# Relay_Cape.net
KiCad netlist of a schematic drawn in EAGLE
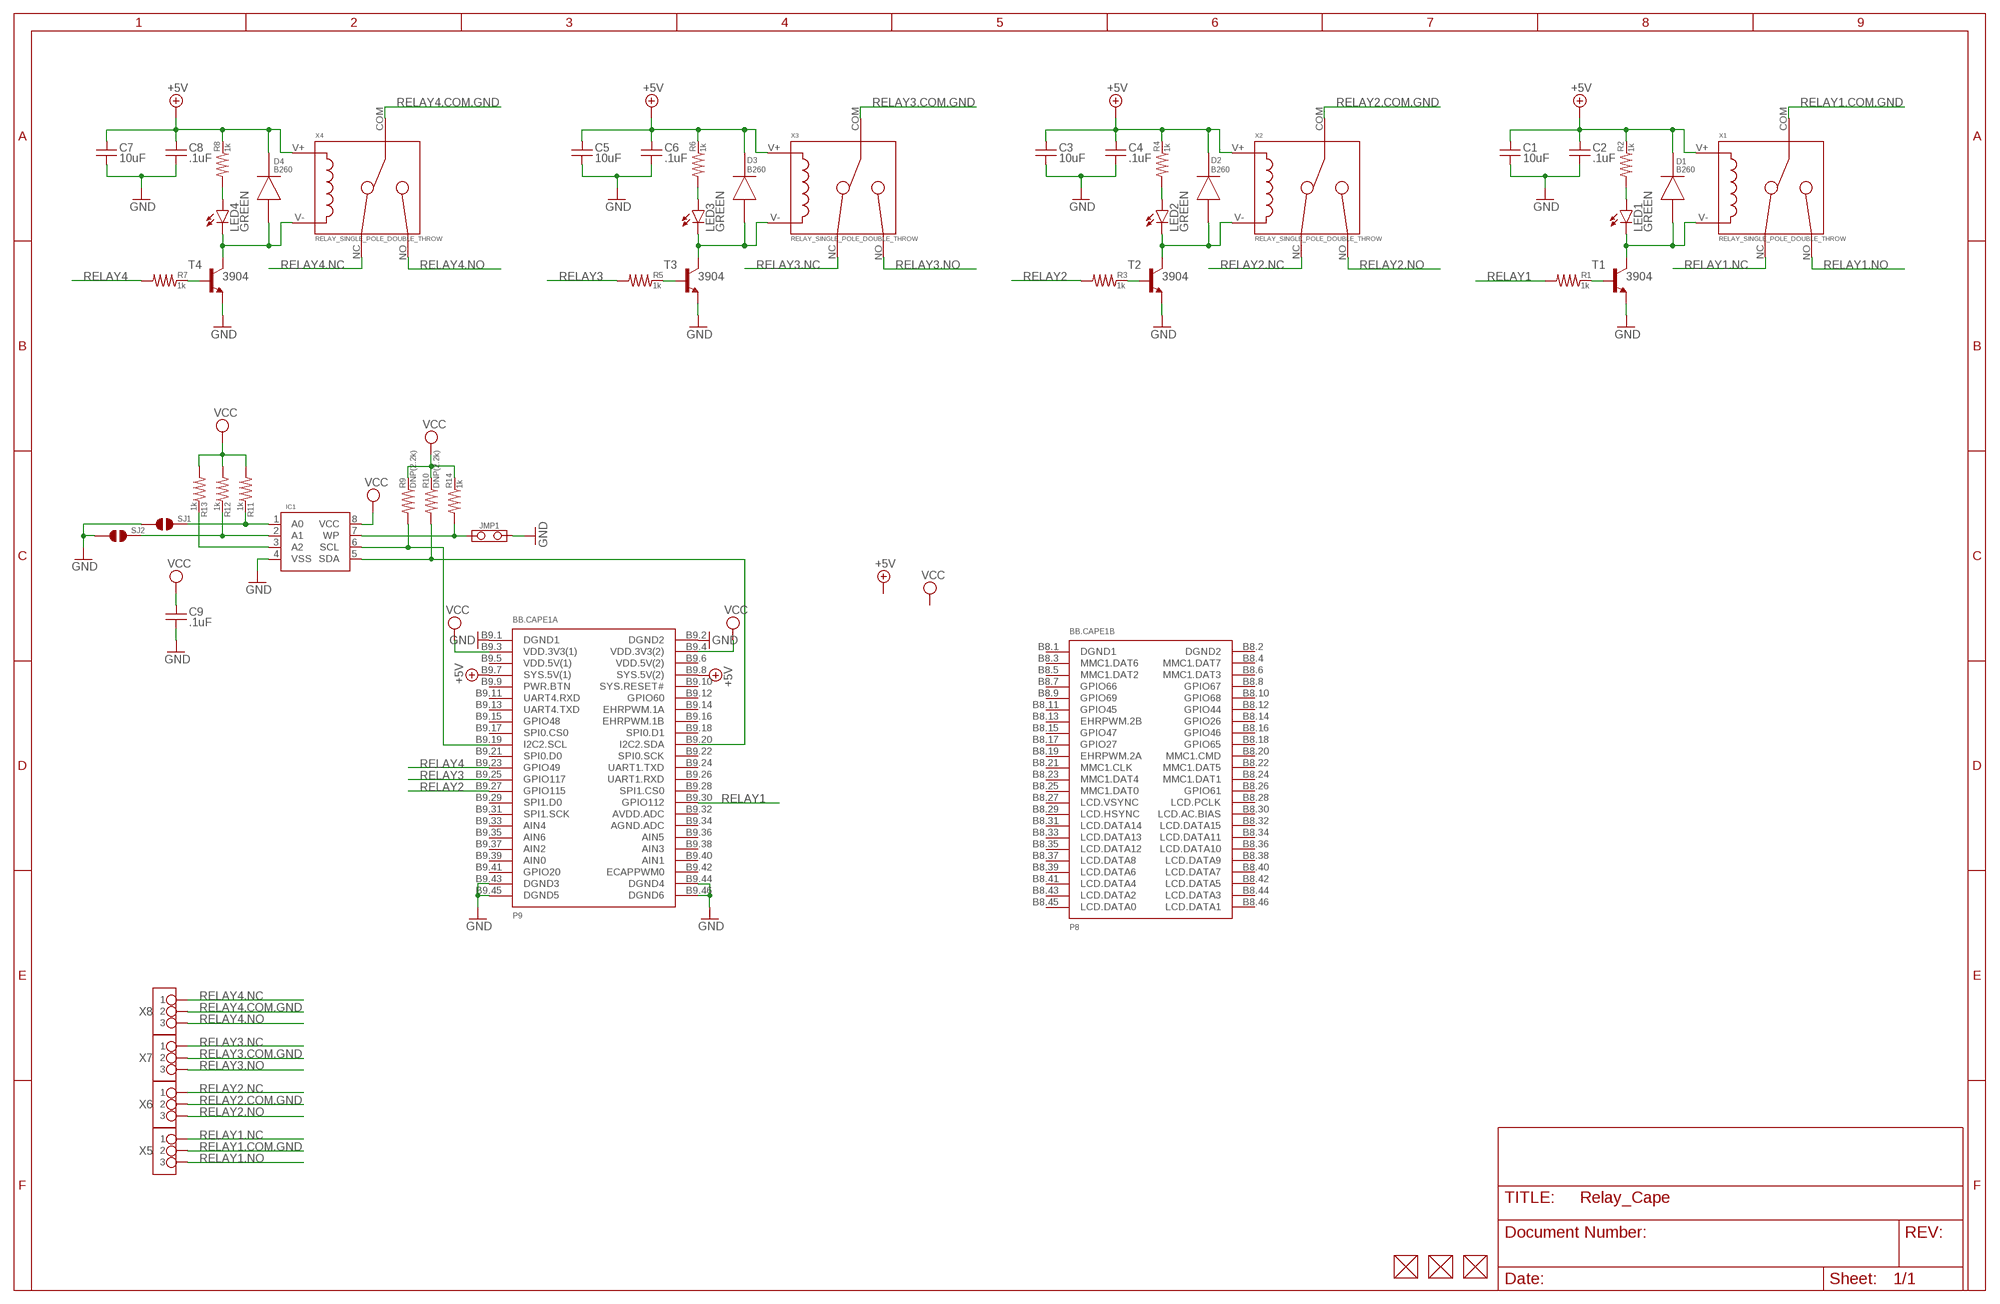
[diagram p0: schematic, sheet 1]

(export (version "E")
  (design (tool "Eeschema 10.0.6"))
  (components
    (comp (ref "BB.CAPE1")
      (value "BEAGLEBONE.CAPE.BOTTOM-ONLY-PADS")
      (footprint "eagle-import:BEAGLEBONE.CAPE.BOTTOM-ONLY-PADS")
      (libsource (lib "eagle-import") (part "BEAGLEBONE.CAPE.BOTTOM-ONLY-PADS"))
    )
    (comp (ref "C1")
      (value "10uF")
      (footprint "eagle-import:0805")
      (libsource (lib "eagle-import") (part "CAPACITOR-(INCH)-0805"))
    )
    (comp (ref "C2")
      (value ".1uF")
      (footprint "eagle-import:0402")
      (libsource (lib "eagle-import") (part "CAPACITOR-(INCH)-0402"))
    )
    (comp (ref "C3")
      (value "10uF")
      (footprint "eagle-import:0805")
      (libsource (lib "eagle-import") (part "CAPACITOR-(INCH)-0805"))
    )
    (comp (ref "C4")
      (value ".1uF")
      (footprint "eagle-import:0402")
      (libsource (lib "eagle-import") (part "CAPACITOR-(INCH)-0402"))
    )
    (comp (ref "C5")
      (value "10uF")
      (footprint "eagle-import:0805")
      (libsource (lib "eagle-import") (part "CAPACITOR-(INCH)-0805"))
    )
    (comp (ref "C6")
      (value ".1uF")
      (footprint "eagle-import:0402")
      (libsource (lib "eagle-import") (part "CAPACITOR-(INCH)-0402"))
    )
    (comp (ref "C7")
      (value "10uF")
      (footprint "eagle-import:0805")
      (libsource (lib "eagle-import") (part "CAPACITOR-(INCH)-0805"))
    )
    (comp (ref "C8")
      (value ".1uF")
      (footprint "eagle-import:0402")
      (libsource (lib "eagle-import") (part "CAPACITOR-(INCH)-0402"))
    )
    (comp (ref "C9")
      (value ".1uF")
      (footprint "eagle-import:0402")
      (libsource (lib "eagle-import") (part "CAPACITOR-(INCH)-0402"))
    )
    (comp (ref "D1")
      (value "B260")
      (footprint "eagle-import:DIODE_SMA")
      (libsource (lib "eagle-import") (part "DIODE_SMA"))
    )
    (comp (ref "D2")
      (value "B260")
      (footprint "eagle-import:DIODE_SMA")
      (libsource (lib "eagle-import") (part "DIODE_SMA"))
    )
    (comp (ref "D3")
      (value "B260")
      (footprint "eagle-import:DIODE_SMA")
      (libsource (lib "eagle-import") (part "DIODE_SMA"))
    )
    (comp (ref "D4")
      (value "B260")
      (footprint "eagle-import:DIODE_SMA")
      (libsource (lib "eagle-import") (part "DIODE_SMA"))
    )
    (comp (ref "FUD1")
      (value "FIDUCIAL")
      (footprint "eagle-import:FIDUCIAL_40MIL")
      (libsource (lib "eagle-import") (part "FIDUCIAL"))
    )
    (comp (ref "FUD2")
      (value "FIDUCIAL")
      (footprint "eagle-import:FIDUCIAL_40MIL")
      (libsource (lib "eagle-import") (part "FIDUCIAL"))
    )
    (comp (ref "FUD3")
      (value "FIDUCIAL")
      (footprint "eagle-import:FIDUCIAL_40MIL")
      (libsource (lib "eagle-import") (part "FIDUCIAL"))
    )
    (comp (ref "IC1")
      (value "CAT24C32")
      (footprint "eagle-import:UDFN8,2X3(ON-SEMI)")
      (libsource (lib "eagle-import") (part "CAT24C32"))
    )
    (comp (ref "JMP1")
      (value "JUMPER-(X2)")
      (footprint "eagle-import:JUMPER-(X2)")
      (libsource (lib "eagle-import") (part "JUMPER-(X2)"))
    )
    (comp (ref "LED1")
      (value "GREEN")
      (footprint "eagle-import:0805-LED")
      (libsource (lib "eagle-import") (part "LED-(INCH)-0805"))
    )
    (comp (ref "LED2")
      (value "GREEN")
      (footprint "eagle-import:0805-LED")
      (libsource (lib "eagle-import") (part "LED-(INCH)-0805"))
    )
    (comp (ref "LED3")
      (value "GREEN")
      (footprint "eagle-import:0805-LED")
      (libsource (lib "eagle-import") (part "LED-(INCH)-0805"))
    )
    (comp (ref "LED4")
      (value "GREEN")
      (footprint "eagle-import:0805-LED")
      (libsource (lib "eagle-import") (part "LED-(INCH)-0805"))
    )
    (comp (ref "R1")
      (value "1k")
      (footprint "eagle-import:0603")
      (libsource (lib "eagle-import") (part "RESISTOR-(INCH)-0603"))
    )
    (comp (ref "R2")
      (value "1k")
      (footprint "eagle-import:0603")
      (libsource (lib "eagle-import") (part "RESISTOR-(INCH)-0603"))
    )
    (comp (ref "R3")
      (value "1k")
      (footprint "eagle-import:0603")
      (libsource (lib "eagle-import") (part "RESISTOR-(INCH)-0603"))
    )
    (comp (ref "R4")
      (value "1k")
      (footprint "eagle-import:0603")
      (libsource (lib "eagle-import") (part "RESISTOR-(INCH)-0603"))
    )
    (comp (ref "R5")
      (value "1k")
      (footprint "eagle-import:0603")
      (libsource (lib "eagle-import") (part "RESISTOR-(INCH)-0603"))
    )
    (comp (ref "R6")
      (value "1k")
      (footprint "eagle-import:0603")
      (libsource (lib "eagle-import") (part "RESISTOR-(INCH)-0603"))
    )
    (comp (ref "R7")
      (value "1k")
      (footprint "eagle-import:0603")
      (libsource (lib "eagle-import") (part "RESISTOR-(INCH)-0603"))
    )
    (comp (ref "R8")
      (value "1k")
      (footprint "eagle-import:0603")
      (libsource (lib "eagle-import") (part "RESISTOR-(INCH)-0603"))
    )
    (comp (ref "R9")
      (value "DNP(2.2k)")
      (footprint "eagle-import:0402")
      (libsource (lib "eagle-import") (part "RESISTOR-(INCH)-0402"))
    )
    (comp (ref "R10")
      (value "DNP(2.2k)")
      (footprint "eagle-import:0402")
      (libsource (lib "eagle-import") (part "RESISTOR-(INCH)-0402"))
    )
    (comp (ref "R11")
      (value "1k")
      (footprint "eagle-import:0402")
      (libsource (lib "eagle-import") (part "RESISTOR-(INCH)-0402"))
    )
    (comp (ref "R12")
      (value "1k")
      (footprint "eagle-import:0402")
      (libsource (lib "eagle-import") (part "RESISTOR-(INCH)-0402"))
    )
    (comp (ref "R13")
      (value "1k")
      (footprint "eagle-import:0402")
      (libsource (lib "eagle-import") (part "RESISTOR-(INCH)-0402"))
    )
    (comp (ref "R14")
      (value "1k")
      (footprint "eagle-import:0402")
      (libsource (lib "eagle-import") (part "RESISTOR-(INCH)-0402"))
    )
    (comp (ref "SJ1")
      (value "SOLDER.JOINT-(INCH)-0603")
      (footprint "eagle-import:SOLDER.JOINT(0603)")
      (libsource (lib "eagle-import") (part "SOLDER.JOINT-(INCH)-0603"))
    )
    (comp (ref "SJ2")
      (value "SOLDER.JOINT-(INCH)-0603")
      (footprint "eagle-import:SOLDER.JOINT(0603)")
      (libsource (lib "eagle-import") (part "SOLDER.JOINT-(INCH)-0603"))
    )
    (comp (ref "T1")
      (value "3904")
      (footprint "eagle-import:SOT23-BEC")
      (libsource (lib "eagle-import") (part "-NPN-SOT23-BECBC847"))
    )
    (comp (ref "T2")
      (value "3904")
      (footprint "eagle-import:SOT23-BEC")
      (libsource (lib "eagle-import") (part "-NPN-SOT23-BECBC847"))
    )
    (comp (ref "T3")
      (value "3904")
      (footprint "eagle-import:SOT23-BEC")
      (libsource (lib "eagle-import") (part "-NPN-SOT23-BECBC847"))
    )
    (comp (ref "T4")
      (value "3904")
      (footprint "eagle-import:SOT23-BEC")
      (libsource (lib "eagle-import") (part "-NPN-SOT23-BECBC847"))
    )
    (comp (ref "X1")
      (value "RELAY_SINGLE_POLE_DOUBLE_THROW")
      (footprint "eagle-import:GOODSKY.RWH-SH-105D")
      (libsource (lib "eagle-import") (part "RELAY_SINGLE_POLE_DOUBLE_THROW"))
    )
    (comp (ref "X2")
      (value "RELAY_SINGLE_POLE_DOUBLE_THROW")
      (footprint "eagle-import:GOODSKY.RWH-SH-105D")
      (libsource (lib "eagle-import") (part "RELAY_SINGLE_POLE_DOUBLE_THROW"))
    )
    (comp (ref "X3")
      (value "RELAY_SINGLE_POLE_DOUBLE_THROW")
      (footprint "eagle-import:GOODSKY.RWH-SH-105D")
      (libsource (lib "eagle-import") (part "RELAY_SINGLE_POLE_DOUBLE_THROW"))
    )
    (comp (ref "X4")
      (value "RELAY_SINGLE_POLE_DOUBLE_THROW")
      (footprint "eagle-import:GOODSKY.RWH-SH-105D")
      (libsource (lib "eagle-import") (part "RELAY_SINGLE_POLE_DOUBLE_THROW"))
    )
    (comp (ref "X5")
      (value "TB-3TERM-5MM.PITCH-(50MIL.HOLES)")
      (footprint "eagle-import:TERMINAL.BLOCK-3TERM-5MM.PITCH-(50MIL.HOLES)")
      (libsource (lib "eagle-import") (part "TB-3TERM-5MM.PITCH-(50MIL.HOLES)"))
    )
    (comp (ref "X6")
      (value "TB-3TERM-5MM.PITCH-(50MIL.HOLES)")
      (footprint "eagle-import:TERMINAL.BLOCK-3TERM-5MM.PITCH-(50MIL.HOLES)")
      (libsource (lib "eagle-import") (part "TB-3TERM-5MM.PITCH-(50MIL.HOLES)"))
    )
    (comp (ref "X7")
      (value "TB-3TERM-5MM.PITCH-(50MIL.HOLES)")
      (footprint "eagle-import:TERMINAL.BLOCK-3TERM-5MM.PITCH-(50MIL.HOLES)")
      (libsource (lib "eagle-import") (part "TB-3TERM-5MM.PITCH-(50MIL.HOLES)"))
    )
    (comp (ref "X8")
      (value "TB-3TERM-5MM.PITCH-(50MIL.HOLES)")
      (footprint "eagle-import:TERMINAL.BLOCK-3TERM-5MM.PITCH-(50MIL.HOLES)")
      (libsource (lib "eagle-import") (part "TB-3TERM-5MM.PITCH-(50MIL.HOLES)"))
    )
  )
  (nets
    (net (code "1") (name "+5V") (class "Default")
      (node (ref "BB.CAPE1") (pin "B9.7") (pinfunction "SYS.5V(1)_B9.7") (pintype "bidirectional"))
      (node (ref "BB.CAPE1") (pin "B9.8") (pinfunction "SYS.5V(2)_B9.8") (pintype "bidirectional"))
      (node (ref "C1") (pin "1") (pinfunction "1_1") (pintype "bidirectional"))
      (node (ref "C2") (pin "1") (pinfunction "1_1") (pintype "bidirectional"))
      (node (ref "C3") (pin "1") (pinfunction "1_1") (pintype "bidirectional"))
      (node (ref "C4") (pin "1") (pinfunction "1_1") (pintype "bidirectional"))
      (node (ref "C5") (pin "1") (pinfunction "1_1") (pintype "bidirectional"))
      (node (ref "C6") (pin "1") (pinfunction "1_1") (pintype "bidirectional"))
      (node (ref "C7") (pin "1") (pinfunction "1_1") (pintype "bidirectional"))
      (node (ref "C8") (pin "1") (pinfunction "1_1") (pintype "bidirectional"))
      (node (ref "D1") (pin "K") (pinfunction "K_K") (pintype "bidirectional"))
      (node (ref "D2") (pin "K") (pinfunction "K_K") (pintype "bidirectional"))
      (node (ref "D3") (pin "K") (pinfunction "K_K") (pintype "bidirectional"))
      (node (ref "D4") (pin "K") (pinfunction "K_K") (pintype "bidirectional"))
      (node (ref "R2") (pin "2") (pinfunction "2_2") (pintype "bidirectional"))
      (node (ref "R4") (pin "2") (pinfunction "2_2") (pintype "bidirectional"))
      (node (ref "R6") (pin "2") (pinfunction "2_2") (pintype "bidirectional"))
      (node (ref "R8") (pin "2") (pinfunction "2_2") (pintype "bidirectional"))
      (node (ref "X1") (pin "V+") (pinfunction "V+_V+") (pintype "bidirectional"))
      (node (ref "X2") (pin "V+") (pinfunction "V+_V+") (pintype "bidirectional"))
      (node (ref "X3") (pin "V+") (pinfunction "V+_V+") (pintype "bidirectional"))
      (node (ref "X4") (pin "V+") (pinfunction "V+_V+") (pintype "bidirectional"))
    )
    (net (code "2") (name "/RELAY1") (class "Default")
      (node (ref "BB.CAPE1") (pin "B9.30") (pinfunction "GPIO112_B9.30") (pintype "bidirectional"))
      (node (ref "R1") (pin "1") (pinfunction "1_1") (pintype "bidirectional"))
    )
    (net (code "3") (name "/RELAY1.COM.GND") (class "Default")
      (node (ref "X1") (pin "COM") (pinfunction "COM_COM") (pintype "bidirectional"))
      (node (ref "X5") (pin "2") (pinfunction "2_2") (pintype "bidirectional"))
    )
    (net (code "4") (name "/RELAY1.NC") (class "Default")
      (node (ref "X1") (pin "NC") (pinfunction "NC_NC") (pintype "bidirectional"))
      (node (ref "X5") (pin "1") (pinfunction "1_1") (pintype "bidirectional"))
    )
    (net (code "5") (name "/RELAY1.NO") (class "Default")
      (node (ref "X1") (pin "NO") (pinfunction "NO_NO") (pintype "bidirectional"))
      (node (ref "X5") (pin "3") (pinfunction "3_3") (pintype "bidirectional"))
    )
    (net (code "6") (name "/RELAY2") (class "Default")
      (node (ref "BB.CAPE1") (pin "B9.27") (pinfunction "GPIO115_B9.27") (pintype "bidirectional"))
      (node (ref "R3") (pin "1") (pinfunction "1_1") (pintype "bidirectional"))
    )
    (net (code "7") (name "/RELAY2.COM.GND") (class "Default")
      (node (ref "X2") (pin "COM") (pinfunction "COM_COM") (pintype "bidirectional"))
      (node (ref "X6") (pin "2") (pinfunction "2_2") (pintype "bidirectional"))
    )
    (net (code "8") (name "/RELAY2.NC") (class "Default")
      (node (ref "X2") (pin "NC") (pinfunction "NC_NC") (pintype "bidirectional"))
      (node (ref "X6") (pin "1") (pinfunction "1_1") (pintype "bidirectional"))
    )
    (net (code "9") (name "/RELAY2.NO") (class "Default")
      (node (ref "X2") (pin "NO") (pinfunction "NO_NO") (pintype "bidirectional"))
      (node (ref "X6") (pin "3") (pinfunction "3_3") (pintype "bidirectional"))
    )
    (net (code "10") (name "/RELAY3") (class "Default")
      (node (ref "BB.CAPE1") (pin "B9.25") (pinfunction "GPIO117_B9.25") (pintype "bidirectional"))
      (node (ref "R5") (pin "1") (pinfunction "1_1") (pintype "bidirectional"))
    )
    (net (code "11") (name "/RELAY3.COM.GND") (class "Default")
      (node (ref "X3") (pin "COM") (pinfunction "COM_COM") (pintype "bidirectional"))
      (node (ref "X7") (pin "2") (pinfunction "2_2") (pintype "bidirectional"))
    )
    (net (code "12") (name "/RELAY3.NC") (class "Default")
      (node (ref "X3") (pin "NC") (pinfunction "NC_NC") (pintype "bidirectional"))
      (node (ref "X7") (pin "1") (pinfunction "1_1") (pintype "bidirectional"))
    )
    (net (code "13") (name "/RELAY3.NO") (class "Default")
      (node (ref "X3") (pin "NO") (pinfunction "NO_NO") (pintype "bidirectional"))
      (node (ref "X7") (pin "3") (pinfunction "3_3") (pintype "bidirectional"))
    )
    (net (code "14") (name "/RELAY4") (class "Default")
      (node (ref "BB.CAPE1") (pin "B9.23") (pinfunction "GPIO49_B9.23") (pintype "bidirectional"))
      (node (ref "R7") (pin "1") (pinfunction "1_1") (pintype "bidirectional"))
    )
    (net (code "15") (name "/RELAY4.COM.GND") (class "Default")
      (node (ref "X4") (pin "COM") (pinfunction "COM_COM") (pintype "bidirectional"))
      (node (ref "X8") (pin "2") (pinfunction "2_2") (pintype "bidirectional"))
    )
    (net (code "16") (name "/RELAY4.NC") (class "Default")
      (node (ref "X4") (pin "NC") (pinfunction "NC_NC") (pintype "bidirectional"))
      (node (ref "X8") (pin "1") (pinfunction "1_1") (pintype "bidirectional"))
    )
    (net (code "17") (name "/RELAY4.NO") (class "Default")
      (node (ref "X4") (pin "NO") (pinfunction "NO_NO") (pintype "bidirectional"))
      (node (ref "X8") (pin "3") (pinfunction "3_3") (pintype "bidirectional"))
    )
    (net (code "18") (name "GND") (class "Default")
      (node (ref "BB.CAPE1") (pin "B9.1") (pinfunction "DGND1_B9.1") (pintype "bidirectional"))
      (node (ref "BB.CAPE1") (pin "B9.2") (pinfunction "DGND2_B9.2") (pintype "bidirectional"))
      (node (ref "BB.CAPE1") (pin "B9.43") (pinfunction "DGND3_B9.43") (pintype "bidirectional"))
      (node (ref "BB.CAPE1") (pin "B9.44") (pinfunction "DGND4_B9.44") (pintype "bidirectional"))
      (node (ref "BB.CAPE1") (pin "B9.45") (pinfunction "DGND5_B9.45") (pintype "bidirectional"))
      (node (ref "BB.CAPE1") (pin "B9.46") (pinfunction "DGND6_B9.46") (pintype "bidirectional"))
      (node (ref "C1") (pin "2") (pinfunction "2_2") (pintype "bidirectional"))
      (node (ref "C2") (pin "2") (pinfunction "2_2") (pintype "bidirectional"))
      (node (ref "C3") (pin "2") (pinfunction "2_2") (pintype "bidirectional"))
      (node (ref "C4") (pin "2") (pinfunction "2_2") (pintype "bidirectional"))
      (node (ref "C5") (pin "2") (pinfunction "2_2") (pintype "bidirectional"))
      (node (ref "C6") (pin "2") (pinfunction "2_2") (pintype "bidirectional"))
      (node (ref "C7") (pin "2") (pinfunction "2_2") (pintype "bidirectional"))
      (node (ref "C8") (pin "2") (pinfunction "2_2") (pintype "bidirectional"))
      (node (ref "C9") (pin "2") (pinfunction "2_2") (pintype "bidirectional"))
      (node (ref "IC1") (pin "4") (pinfunction "VSS_4") (pintype "bidirectional"))
      (node (ref "JMP1") (pin "2") (pinfunction "2_2") (pintype "bidirectional"))
      (node (ref "SJ1") (pin "1") (pinfunction "1_1") (pintype "bidirectional"))
      (node (ref "SJ2") (pin "1") (pinfunction "1_1") (pintype "bidirectional"))
      (node (ref "T1") (pin "E") (pinfunction "E_E") (pintype "passive"))
      (node (ref "T2") (pin "E") (pinfunction "E_E") (pintype "passive"))
      (node (ref "T3") (pin "E") (pinfunction "E_E") (pintype "passive"))
      (node (ref "T4") (pin "E") (pinfunction "E_E") (pintype "passive"))
    )
    (net (code "19") (name "Net-(BB.CAPE1A-I2C2.SCL)") (class "Default")
      (node (ref "BB.CAPE1") (pin "B9.19") (pinfunction "I2C2.SCL_B9.19") (pintype "bidirectional"))
      (node (ref "IC1") (pin "6") (pinfunction "SCL_6") (pintype "bidirectional"))
      (node (ref "R9") (pin "1") (pinfunction "1_1") (pintype "bidirectional"))
    )
    (net (code "20") (name "Net-(BB.CAPE1A-I2C2.SDA)") (class "Default")
      (node (ref "BB.CAPE1") (pin "B9.20") (pinfunction "I2C2.SDA_B9.20") (pintype "bidirectional"))
      (node (ref "IC1") (pin "5") (pinfunction "SDA_5") (pintype "bidirectional"))
      (node (ref "R10") (pin "1") (pinfunction "1_1") (pintype "bidirectional"))
    )
    (net (code "21") (name "Net-(D1-PadA)") (class "Default")
      (node (ref "D1") (pin "A") (pinfunction "A_A") (pintype "bidirectional"))
      (node (ref "LED1") (pin "K") (pinfunction "K_K") (pintype "passive"))
      (node (ref "T1") (pin "C") (pinfunction "C_C") (pintype "passive"))
      (node (ref "X1") (pin "V-") (pinfunction "V-_V-") (pintype "bidirectional"))
    )
    (net (code "22") (name "Net-(D2-PadA)") (class "Default")
      (node (ref "D2") (pin "A") (pinfunction "A_A") (pintype "bidirectional"))
      (node (ref "LED2") (pin "K") (pinfunction "K_K") (pintype "passive"))
      (node (ref "T2") (pin "C") (pinfunction "C_C") (pintype "passive"))
      (node (ref "X2") (pin "V-") (pinfunction "V-_V-") (pintype "bidirectional"))
    )
    (net (code "23") (name "Net-(D3-PadA)") (class "Default")
      (node (ref "D3") (pin "A") (pinfunction "A_A") (pintype "bidirectional"))
      (node (ref "LED3") (pin "K") (pinfunction "K_K") (pintype "passive"))
      (node (ref "T3") (pin "C") (pinfunction "C_C") (pintype "passive"))
      (node (ref "X3") (pin "V-") (pinfunction "V-_V-") (pintype "bidirectional"))
    )
    (net (code "24") (name "Net-(D4-PadA)") (class "Default")
      (node (ref "D4") (pin "A") (pinfunction "A_A") (pintype "bidirectional"))
      (node (ref "LED4") (pin "K") (pinfunction "K_K") (pintype "passive"))
      (node (ref "T4") (pin "C") (pinfunction "C_C") (pintype "passive"))
      (node (ref "X4") (pin "V-") (pinfunction "V-_V-") (pintype "bidirectional"))
    )
    (net (code "25") (name "Net-(IC1-A0)") (class "Default")
      (node (ref "IC1") (pin "1") (pinfunction "A0_1") (pintype "bidirectional"))
      (node (ref "R11") (pin "2") (pinfunction "2_2") (pintype "bidirectional"))
      (node (ref "SJ1") (pin "2") (pinfunction "2_2") (pintype "bidirectional"))
    )
    (net (code "26") (name "Net-(IC1-A1)") (class "Default")
      (node (ref "IC1") (pin "2") (pinfunction "A1_2") (pintype "bidirectional"))
      (node (ref "R12") (pin "2") (pinfunction "2_2") (pintype "bidirectional"))
      (node (ref "SJ2") (pin "2") (pinfunction "2_2") (pintype "bidirectional"))
    )
    (net (code "27") (name "Net-(IC1-A2)") (class "Default")
      (node (ref "IC1") (pin "3") (pinfunction "A2_3") (pintype "bidirectional"))
      (node (ref "R13") (pin "2") (pinfunction "2_2") (pintype "bidirectional"))
    )
    (net (code "28") (name "Net-(IC1-WP)") (class "Default")
      (node (ref "IC1") (pin "7") (pinfunction "WP_7") (pintype "bidirectional"))
      (node (ref "JMP1") (pin "1") (pinfunction "1_1") (pintype "bidirectional"))
      (node (ref "R14") (pin "1") (pinfunction "1_1") (pintype "bidirectional"))
    )
    (net (code "29") (name "Net-(LED1-PadA)") (class "Default")
      (node (ref "LED1") (pin "A") (pinfunction "A_A") (pintype "passive"))
      (node (ref "R2") (pin "1") (pinfunction "1_1") (pintype "bidirectional"))
    )
    (net (code "30") (name "Net-(LED2-PadA)") (class "Default")
      (node (ref "LED2") (pin "A") (pinfunction "A_A") (pintype "passive"))
      (node (ref "R4") (pin "1") (pinfunction "1_1") (pintype "bidirectional"))
    )
    (net (code "31") (name "Net-(LED3-PadA)") (class "Default")
      (node (ref "LED3") (pin "A") (pinfunction "A_A") (pintype "passive"))
      (node (ref "R6") (pin "1") (pinfunction "1_1") (pintype "bidirectional"))
    )
    (net (code "32") (name "Net-(LED4-PadA)") (class "Default")
      (node (ref "LED4") (pin "A") (pinfunction "A_A") (pintype "passive"))
      (node (ref "R8") (pin "1") (pinfunction "1_1") (pintype "bidirectional"))
    )
    (net (code "33") (name "Net-(R1-Pad2)") (class "Default")
      (node (ref "R1") (pin "2") (pinfunction "2_2") (pintype "bidirectional"))
      (node (ref "T1") (pin "B") (pinfunction "B_B") (pintype "passive"))
    )
    (net (code "34") (name "Net-(R3-Pad2)") (class "Default")
      (node (ref "R3") (pin "2") (pinfunction "2_2") (pintype "bidirectional"))
      (node (ref "T2") (pin "B") (pinfunction "B_B") (pintype "passive"))
    )
    (net (code "35") (name "Net-(R5-Pad2)") (class "Default")
      (node (ref "R5") (pin "2") (pinfunction "2_2") (pintype "bidirectional"))
      (node (ref "T3") (pin "B") (pinfunction "B_B") (pintype "passive"))
    )
    (net (code "36") (name "Net-(R7-Pad2)") (class "Default")
      (node (ref "R7") (pin "2") (pinfunction "2_2") (pintype "bidirectional"))
      (node (ref "T4") (pin "B") (pinfunction "B_B") (pintype "passive"))
    )
    (net (code "37") (name "VCC") (class "Default")
      (node (ref "BB.CAPE1") (pin "B9.3") (pinfunction "VDD.3V3(1)_B9.3") (pintype "bidirectional"))
      (node (ref "BB.CAPE1") (pin "B9.4") (pinfunction "VDD.3V3(2)_B9.4") (pintype "bidirectional"))
      (node (ref "C9") (pin "1") (pinfunction "1_1") (pintype "bidirectional"))
      (node (ref "IC1") (pin "8") (pinfunction "VCC_8") (pintype "bidirectional"))
      (node (ref "R10") (pin "2") (pinfunction "2_2") (pintype "bidirectional"))
      (node (ref "R11") (pin "1") (pinfunction "1_1") (pintype "bidirectional"))
      (node (ref "R12") (pin "1") (pinfunction "1_1") (pintype "bidirectional"))
      (node (ref "R13") (pin "1") (pinfunction "1_1") (pintype "bidirectional"))
      (node (ref "R14") (pin "2") (pinfunction "2_2") (pintype "bidirectional"))
      (node (ref "R9") (pin "2") (pinfunction "2_2") (pintype "bidirectional"))
    )
    (net (code "38") (name "unconnected-(BB.CAPE1A-AGND.ADC-PadB9.34)") (class "Default")
      (node (ref "BB.CAPE1") (pin "B9.34") (pinfunction "AGND.ADC_B9.34") (pintype "bidirectional"))
    )
    (net (code "39") (name "unconnected-(BB.CAPE1A-AIN0-PadB9.39)") (class "Default")
      (node (ref "BB.CAPE1") (pin "B9.39") (pinfunction "AIN0_B9.39") (pintype "bidirectional"))
    )
    (net (code "40") (name "unconnected-(BB.CAPE1A-AIN1-PadB9.40)") (class "Default")
      (node (ref "BB.CAPE1") (pin "B9.40") (pinfunction "AIN1_B9.40") (pintype "bidirectional"))
    )
    (net (code "41") (name "unconnected-(BB.CAPE1A-AIN2-PadB9.37)") (class "Default")
      (node (ref "BB.CAPE1") (pin "B9.37") (pinfunction "AIN2_B9.37") (pintype "bidirectional"))
    )
    (net (code "42") (name "unconnected-(BB.CAPE1A-AIN3-PadB9.38)") (class "Default")
      (node (ref "BB.CAPE1") (pin "B9.38") (pinfunction "AIN3_B9.38") (pintype "bidirectional"))
    )
    (net (code "43") (name "unconnected-(BB.CAPE1A-AIN4-PadB9.33)") (class "Default")
      (node (ref "BB.CAPE1") (pin "B9.33") (pinfunction "AIN4_B9.33") (pintype "bidirectional"))
    )
    (net (code "44") (name "unconnected-(BB.CAPE1A-AIN5-PadB9.36)") (class "Default")
      (node (ref "BB.CAPE1") (pin "B9.36") (pinfunction "AIN5_B9.36") (pintype "bidirectional"))
    )
    (net (code "45") (name "unconnected-(BB.CAPE1A-AIN6-PadB9.35)") (class "Default")
      (node (ref "BB.CAPE1") (pin "B9.35") (pinfunction "AIN6_B9.35") (pintype "bidirectional"))
    )
    (net (code "46") (name "unconnected-(BB.CAPE1A-AVDD.ADC-PadB9.32)") (class "Default")
      (node (ref "BB.CAPE1") (pin "B9.32") (pinfunction "AVDD.ADC_B9.32") (pintype "bidirectional"))
    )
    (net (code "47") (name "unconnected-(BB.CAPE1A-ECAPPWM0-PadB9.42)") (class "Default")
      (node (ref "BB.CAPE1") (pin "B9.42") (pinfunction "ECAPPWM0_B9.42") (pintype "bidirectional"))
    )
    (net (code "48") (name "unconnected-(BB.CAPE1A-EHRPWM.1A-PadB9.14)") (class "Default")
      (node (ref "BB.CAPE1") (pin "B9.14") (pinfunction "EHRPWM.1A_B9.14") (pintype "bidirectional"))
    )
    (net (code "49") (name "unconnected-(BB.CAPE1A-EHRPWM.1B-PadB9.16)") (class "Default")
      (node (ref "BB.CAPE1") (pin "B9.16") (pinfunction "EHRPWM.1B_B9.16") (pintype "bidirectional"))
    )
    (net (code "50") (name "unconnected-(BB.CAPE1A-GPIO20-PadB9.41)") (class "Default")
      (node (ref "BB.CAPE1") (pin "B9.41") (pinfunction "GPIO20_B9.41") (pintype "bidirectional"))
    )
    (net (code "51") (name "unconnected-(BB.CAPE1A-GPIO48-PadB9.15)") (class "Default")
      (node (ref "BB.CAPE1") (pin "B9.15") (pinfunction "GPIO48_B9.15") (pintype "bidirectional"))
    )
    (net (code "52") (name "unconnected-(BB.CAPE1A-GPIO60-PadB9.12)") (class "Default")
      (node (ref "BB.CAPE1") (pin "B9.12") (pinfunction "GPIO60_B9.12") (pintype "bidirectional"))
    )
    (net (code "53") (name "unconnected-(BB.CAPE1A-PWR.BTN-PadB9.9)") (class "Default")
      (node (ref "BB.CAPE1") (pin "B9.9") (pinfunction "PWR.BTN_B9.9") (pintype "bidirectional"))
    )
    (net (code "54") (name "unconnected-(BB.CAPE1A-SPI0.CS0-PadB9.17)") (class "Default")
      (node (ref "BB.CAPE1") (pin "B9.17") (pinfunction "SPI0.CS0_B9.17") (pintype "bidirectional"))
    )
    (net (code "55") (name "unconnected-(BB.CAPE1A-SPI0.D0-PadB9.21)") (class "Default")
      (node (ref "BB.CAPE1") (pin "B9.21") (pinfunction "SPI0.D0_B9.21") (pintype "bidirectional"))
    )
    (net (code "56") (name "unconnected-(BB.CAPE1A-SPI0.D1-PadB9.18)") (class "Default")
      (node (ref "BB.CAPE1") (pin "B9.18") (pinfunction "SPI0.D1_B9.18") (pintype "bidirectional"))
    )
    (net (code "57") (name "unconnected-(BB.CAPE1A-SPI0.SCK-PadB9.22)") (class "Default")
      (node (ref "BB.CAPE1") (pin "B9.22") (pinfunction "SPI0.SCK_B9.22") (pintype "bidirectional"))
    )
    (net (code "58") (name "unconnected-(BB.CAPE1A-SPI1.CS0-PadB9.28)") (class "Default")
      (node (ref "BB.CAPE1") (pin "B9.28") (pinfunction "SPI1.CS0_B9.28") (pintype "bidirectional"))
    )
    (net (code "59") (name "unconnected-(BB.CAPE1A-SPI1.D0-PadB9.29)") (class "Default")
      (node (ref "BB.CAPE1") (pin "B9.29") (pinfunction "SPI1.D0_B9.29") (pintype "bidirectional"))
    )
    (net (code "60") (name "unconnected-(BB.CAPE1A-SPI1.SCK-PadB9.31)") (class "Default")
      (node (ref "BB.CAPE1") (pin "B9.31") (pinfunction "SPI1.SCK_B9.31") (pintype "bidirectional"))
    )
    (net (code "61") (name "unconnected-(BB.CAPE1A-SYS.RESET#-PadB9.10)") (class "Default")
      (node (ref "BB.CAPE1") (pin "B9.10") (pinfunction "SYS.RESET#_B9.10") (pintype "bidirectional"))
    )
    (net (code "62") (name "unconnected-(BB.CAPE1A-UART1.RXD-PadB9.26)") (class "Default")
      (node (ref "BB.CAPE1") (pin "B9.26") (pinfunction "UART1.RXD_B9.26") (pintype "bidirectional"))
    )
    (net (code "63") (name "unconnected-(BB.CAPE1A-UART1.TXD-PadB9.24)") (class "Default")
      (node (ref "BB.CAPE1") (pin "B9.24") (pinfunction "UART1.TXD_B9.24") (pintype "bidirectional"))
    )
    (net (code "64") (name "unconnected-(BB.CAPE1A-UART4.RXD-PadB9.11)") (class "Default")
      (node (ref "BB.CAPE1") (pin "B9.11") (pinfunction "UART4.RXD_B9.11") (pintype "bidirectional"))
    )
    (net (code "65") (name "unconnected-(BB.CAPE1A-UART4.TXD-PadB9.13)") (class "Default")
      (node (ref "BB.CAPE1") (pin "B9.13") (pinfunction "UART4.TXD_B9.13") (pintype "bidirectional"))
    )
    (net (code "66") (name "unconnected-(BB.CAPE1A-VDD.5V(1)-PadB9.5)") (class "Default")
      (node (ref "BB.CAPE1") (pin "B9.5") (pinfunction "VDD.5V(1)_B9.5") (pintype "bidirectional"))
    )
    (net (code "67") (name "unconnected-(BB.CAPE1A-VDD.5V(2)-PadB9.6)") (class "Default")
      (node (ref "BB.CAPE1") (pin "B9.6") (pinfunction "VDD.5V(2)_B9.6") (pintype "bidirectional"))
    )
    (net (code "68") (name "unconnected-(BB.CAPE1B-DGND1-PadB8.1)") (class "Default")
      (node (ref "BB.CAPE1") (pin "B8.1") (pinfunction "DGND1_B8.1") (pintype "bidirectional"))
    )
    (net (code "69") (name "unconnected-(BB.CAPE1B-DGND2-PadB8.2)") (class "Default")
      (node (ref "BB.CAPE1") (pin "B8.2") (pinfunction "DGND2_B8.2") (pintype "bidirectional"))
    )
    (net (code "70") (name "unconnected-(BB.CAPE1B-EHRPWM.2A-PadB8.19)") (class "Default")
      (node (ref "BB.CAPE1") (pin "B8.19") (pinfunction "EHRPWM.2A_B8.19") (pintype "bidirectional"))
    )
    (net (code "71") (name "unconnected-(BB.CAPE1B-EHRPWM.2B-PadB8.13)") (class "Default")
      (node (ref "BB.CAPE1") (pin "B8.13") (pinfunction "EHRPWM.2B_B8.13") (pintype "bidirectional"))
    )
    (net (code "72") (name "unconnected-(BB.CAPE1B-GPIO26-PadB8.14)") (class "Default")
      (node (ref "BB.CAPE1") (pin "B8.14") (pinfunction "GPIO26_B8.14") (pintype "bidirectional"))
    )
    (net (code "73") (name "unconnected-(BB.CAPE1B-GPIO27-PadB8.17)") (class "Default")
      (node (ref "BB.CAPE1") (pin "B8.17") (pinfunction "GPIO27_B8.17") (pintype "bidirectional"))
    )
    (net (code "74") (name "unconnected-(BB.CAPE1B-GPIO44-PadB8.12)") (class "Default")
      (node (ref "BB.CAPE1") (pin "B8.12") (pinfunction "GPIO44_B8.12") (pintype "bidirectional"))
    )
    (net (code "75") (name "unconnected-(BB.CAPE1B-GPIO45-PadB8.11)") (class "Default")
      (node (ref "BB.CAPE1") (pin "B8.11") (pinfunction "GPIO45_B8.11") (pintype "bidirectional"))
    )
    (net (code "76") (name "unconnected-(BB.CAPE1B-GPIO46-PadB8.16)") (class "Default")
      (node (ref "BB.CAPE1") (pin "B8.16") (pinfunction "GPIO46_B8.16") (pintype "bidirectional"))
    )
    (net (code "77") (name "unconnected-(BB.CAPE1B-GPIO47-PadB8.15)") (class "Default")
      (node (ref "BB.CAPE1") (pin "B8.15") (pinfunction "GPIO47_B8.15") (pintype "bidirectional"))
    )
    (net (code "78") (name "unconnected-(BB.CAPE1B-GPIO61-PadB8.26)") (class "Default")
      (node (ref "BB.CAPE1") (pin "B8.26") (pinfunction "GPIO61_B8.26") (pintype "bidirectional"))
    )
    (net (code "79") (name "unconnected-(BB.CAPE1B-GPIO65-PadB8.18)") (class "Default")
      (node (ref "BB.CAPE1") (pin "B8.18") (pinfunction "GPIO65_B8.18") (pintype "bidirectional"))
    )
    (net (code "80") (name "unconnected-(BB.CAPE1B-GPIO66-PadB8.7)") (class "Default")
      (node (ref "BB.CAPE1") (pin "B8.7") (pinfunction "GPIO66_B8.7") (pintype "bidirectional"))
    )
    (net (code "81") (name "unconnected-(BB.CAPE1B-GPIO67-PadB8.8)") (class "Default")
      (node (ref "BB.CAPE1") (pin "B8.8") (pinfunction "GPIO67_B8.8") (pintype "bidirectional"))
    )
    (net (code "82") (name "unconnected-(BB.CAPE1B-GPIO68-PadB8.10)") (class "Default")
      (node (ref "BB.CAPE1") (pin "B8.10") (pinfunction "GPIO68_B8.10") (pintype "bidirectional"))
    )
    (net (code "83") (name "unconnected-(BB.CAPE1B-GPIO69-PadB8.9)") (class "Default")
      (node (ref "BB.CAPE1") (pin "B8.9") (pinfunction "GPIO69_B8.9") (pintype "bidirectional"))
    )
    (net (code "84") (name "unconnected-(BB.CAPE1B-LCD.AC.BIAS-PadB8.30)") (class "Default")
      (node (ref "BB.CAPE1") (pin "B8.30") (pinfunction "LCD.AC.BIAS_B8.30") (pintype "bidirectional"))
    )
    (net (code "85") (name "unconnected-(BB.CAPE1B-LCD.DATA0-PadB8.45)") (class "Default")
      (node (ref "BB.CAPE1") (pin "B8.45") (pinfunction "LCD.DATA0_B8.45") (pintype "bidirectional"))
    )
    (net (code "86") (name "unconnected-(BB.CAPE1B-LCD.DATA1-PadB8.46)") (class "Default")
      (node (ref "BB.CAPE1") (pin "B8.46") (pinfunction "LCD.DATA1_B8.46") (pintype "bidirectional"))
    )
    (net (code "87") (name "unconnected-(BB.CAPE1B-LCD.DATA2-PadB8.43)") (class "Default")
      (node (ref "BB.CAPE1") (pin "B8.43") (pinfunction "LCD.DATA2_B8.43") (pintype "bidirectional"))
    )
    (net (code "88") (name "unconnected-(BB.CAPE1B-LCD.DATA3-PadB8.44)") (class "Default")
      (node (ref "BB.CAPE1") (pin "B8.44") (pinfunction "LCD.DATA3_B8.44") (pintype "bidirectional"))
    )
    (net (code "89") (name "unconnected-(BB.CAPE1B-LCD.DATA4-PadB8.41)") (class "Default")
      (node (ref "BB.CAPE1") (pin "B8.41") (pinfunction "LCD.DATA4_B8.41") (pintype "bidirectional"))
    )
    (net (code "90") (name "unconnected-(BB.CAPE1B-LCD.DATA5-PadB8.42)") (class "Default")
      (node (ref "BB.CAPE1") (pin "B8.42") (pinfunction "LCD.DATA5_B8.42") (pintype "bidirectional"))
    )
    (net (code "91") (name "unconnected-(BB.CAPE1B-LCD.DATA6-PadB8.39)") (class "Default")
      (node (ref "BB.CAPE1") (pin "B8.39") (pinfunction "LCD.DATA6_B8.39") (pintype "bidirectional"))
    )
    (net (code "92") (name "unconnected-(BB.CAPE1B-LCD.DATA7-PadB8.40)") (class "Default")
      (node (ref "BB.CAPE1") (pin "B8.40") (pinfunction "LCD.DATA7_B8.40") (pintype "bidirectional"))
    )
    (net (code "93") (name "unconnected-(BB.CAPE1B-LCD.DATA8-PadB8.37)") (class "Default")
      (node (ref "BB.CAPE1") (pin "B8.37") (pinfunction "LCD.DATA8_B8.37") (pintype "bidirectional"))
    )
    (net (code "94") (name "unconnected-(BB.CAPE1B-LCD.DATA9-PadB8.38)") (class "Default")
      (node (ref "BB.CAPE1") (pin "B8.38") (pinfunction "LCD.DATA9_B8.38") (pintype "bidirectional"))
    )
    (net (code "95") (name "unconnected-(BB.CAPE1B-LCD.DATA10-PadB8.36)") (class "Default")
      (node (ref "BB.CAPE1") (pin "B8.36") (pinfunction "LCD.DATA10_B8.36") (pintype "bidirectional"))
    )
    (net (code "96") (name "unconnected-(BB.CAPE1B-LCD.DATA11-PadB8.34)") (class "Default")
      (node (ref "BB.CAPE1") (pin "B8.34") (pinfunction "LCD.DATA11_B8.34") (pintype "bidirectional"))
    )
    (net (code "97") (name "unconnected-(BB.CAPE1B-LCD.DATA12-PadB8.35)") (class "Default")
      (node (ref "BB.CAPE1") (pin "B8.35") (pinfunction "LCD.DATA12_B8.35") (pintype "bidirectional"))
    )
    (net (code "98") (name "unconnected-(BB.CAPE1B-LCD.DATA13-PadB8.33)") (class "Default")
      (node (ref "BB.CAPE1") (pin "B8.33") (pinfunction "LCD.DATA13_B8.33") (pintype "bidirectional"))
    )
    (net (code "99") (name "unconnected-(BB.CAPE1B-LCD.DATA14-PadB8.31)") (class "Default")
      (node (ref "BB.CAPE1") (pin "B8.31") (pinfunction "LCD.DATA14_B8.31") (pintype "bidirectional"))
    )
    (net (code "100") (name "unconnected-(BB.CAPE1B-LCD.DATA15-PadB8.32)") (class "Default")
      (node (ref "BB.CAPE1") (pin "B8.32") (pinfunction "LCD.DATA15_B8.32") (pintype "bidirectional"))
    )
    (net (code "101") (name "unconnected-(BB.CAPE1B-LCD.HSYNC-PadB8.29)") (class "Default")
      (node (ref "BB.CAPE1") (pin "B8.29") (pinfunction "LCD.HSYNC_B8.29") (pintype "bidirectional"))
    )
    (net (code "102") (name "unconnected-(BB.CAPE1B-LCD.PCLK-PadB8.28)") (class "Default")
      (node (ref "BB.CAPE1") (pin "B8.28") (pinfunction "LCD.PCLK_B8.28") (pintype "bidirectional"))
    )
    (net (code "103") (name "unconnected-(BB.CAPE1B-LCD.VSYNC-PadB8.27)") (class "Default")
      (node (ref "BB.CAPE1") (pin "B8.27") (pinfunction "LCD.VSYNC_B8.27") (pintype "bidirectional"))
    )
    (net (code "104") (name "unconnected-(BB.CAPE1B-MMC1.CLK-PadB8.21)") (class "Default")
      (node (ref "BB.CAPE1") (pin "B8.21") (pinfunction "MMC1.CLK_B8.21") (pintype "bidirectional"))
    )
    (net (code "105") (name "unconnected-(BB.CAPE1B-MMC1.CMD-PadB8.20)") (class "Default")
      (node (ref "BB.CAPE1") (pin "B8.20") (pinfunction "MMC1.CMD_B8.20") (pintype "bidirectional"))
    )
    (net (code "106") (name "unconnected-(BB.CAPE1B-MMC1.DAT0-PadB8.25)") (class "Default")
      (node (ref "BB.CAPE1") (pin "B8.25") (pinfunction "MMC1.DAT0_B8.25") (pintype "bidirectional"))
    )
    (net (code "107") (name "unconnected-(BB.CAPE1B-MMC1.DAT1-PadB8.24)") (class "Default")
      (node (ref "BB.CAPE1") (pin "B8.24") (pinfunction "MMC1.DAT1_B8.24") (pintype "bidirectional"))
    )
    (net (code "108") (name "unconnected-(BB.CAPE1B-MMC1.DAT2-PadB8.5)") (class "Default")
      (node (ref "BB.CAPE1") (pin "B8.5") (pinfunction "MMC1.DAT2_B8.5") (pintype "bidirectional"))
    )
    (net (code "109") (name "unconnected-(BB.CAPE1B-MMC1.DAT3-PadB8.6)") (class "Default")
      (node (ref "BB.CAPE1") (pin "B8.6") (pinfunction "MMC1.DAT3_B8.6") (pintype "bidirectional"))
    )
    (net (code "110") (name "unconnected-(BB.CAPE1B-MMC1.DAT4-PadB8.23)") (class "Default")
      (node (ref "BB.CAPE1") (pin "B8.23") (pinfunction "MMC1.DAT4_B8.23") (pintype "bidirectional"))
    )
    (net (code "111") (name "unconnected-(BB.CAPE1B-MMC1.DAT5-PadB8.22)") (class "Default")
      (node (ref "BB.CAPE1") (pin "B8.22") (pinfunction "MMC1.DAT5_B8.22") (pintype "bidirectional"))
    )
    (net (code "112") (name "unconnected-(BB.CAPE1B-MMC1.DAT6-PadB8.3)") (class "Default")
      (node (ref "BB.CAPE1") (pin "B8.3") (pinfunction "MMC1.DAT6_B8.3") (pintype "bidirectional"))
    )
    (net (code "113") (name "unconnected-(BB.CAPE1B-MMC1.DAT7-PadB8.4)") (class "Default")
      (node (ref "BB.CAPE1") (pin "B8.4") (pinfunction "MMC1.DAT7_B8.4") (pintype "bidirectional"))
    )
    (net (code "114") (name "unconnected-(FUD1-PadP$1)") (class "Default")
      (node (ref "FUD1") (pin "P$1") (pinfunction "P$1_P$1") (pintype "no_connect"))
    )
    (net (code "115") (name "unconnected-(FUD2-PadP$1)") (class "Default")
      (node (ref "FUD2") (pin "P$1") (pinfunction "P$1_P$1") (pintype "no_connect"))
    )
    (net (code "116") (name "unconnected-(FUD3-PadP$1)") (class "Default")
      (node (ref "FUD3") (pin "P$1") (pinfunction "P$1_P$1") (pintype "no_connect"))
    )
  )
)
